# Power.net
KiCad netlist of a schematic drawn in Altium Designer
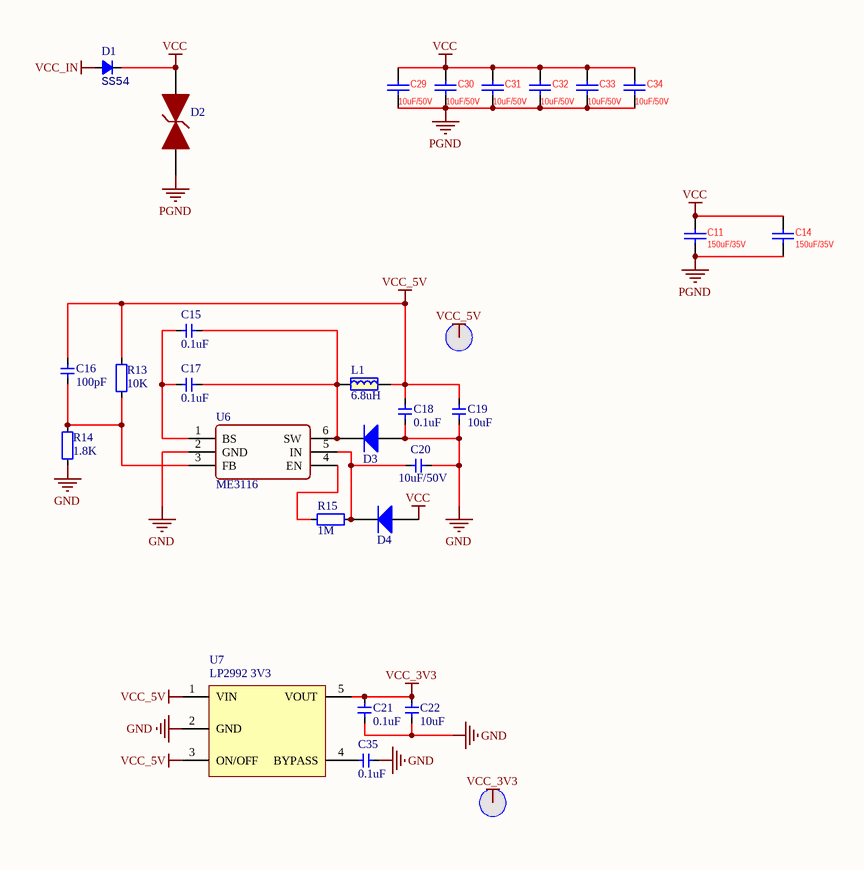
[diagram p0: Power.SchDoc]

(export (version "E")
  (design (tool "Eeschema 10.0.6"))
  (components
    (comp (ref "C11")
      (value "150uF/35V")
      (footprint "CAP-SMD_BD8.0-L8.3-W8.3-LS9.3-FD")
      (description "Capacitor, chip, ceramic")
      (fields (field (name "Comment") "220uF/25V"))
      (libsource (lib "OAKUSBFXS") (part "CAP"))
    )
    (comp (ref "C14")
      (value "150uF/35V")
      (footprint "CAP-SMD_BD8.0-L8.3-W8.3-LS9.3-FD")
      (description "Capacitor, chip, ceramic")
      (fields (field (name "Comment") "220uF/25V"))
      (libsource (lib "OAKUSBFXS") (part "CAP"))
    )
    (comp (ref "C15")
      (value "0.1uF")
      (footprint "motor42-lib:CAP_0402")
      (description "Capacitor")
      (libsource (lib "MyPcbLib") (part "电容-0402"))
    )
    (comp (ref "C16")
      (value "100pF")
      (footprint "CAP_0402")
      (description "Capacitor")
      (libsource (lib "MyPcbLib") (part "电容-0402"))
    )
    (comp (ref "C17")
      (value "0.1uF")
      (footprint "motor42-lib:CAP_0402")
      (description "Capacitor")
      (libsource (lib "MyPcbLib") (part "电容-0402"))
    )
    (comp (ref "C18")
      (value "0.1uF")
      (footprint "motor42-lib:CAP_0402")
      (description "Capacitor")
      (libsource (lib "MyPcbLib") (part "电容-0402"))
    )
    (comp (ref "C19")
      (value "10uF")
      (footprint "CAP_0402")
      (description "Capacitor")
      (libsource (lib "MyPcbLib") (part "电容-0402"))
    )
    (comp (ref "C20")
      (value "10uF/50V")
      (footprint "1206-CAP")
      (description "Capacitor")
      (libsource (lib "MyPcbLib") (part "电容-0402"))
    )
    (comp (ref "C21")
      (value "0.1uF")
      (footprint "motor42-lib:CAP_0402")
      (description "Capacitor")
      (libsource (lib "MyPcbLib") (part "电容-0402"))
    )
    (comp (ref "C22")
      (value "10uF")
      (footprint "CAP_0402")
      (description "Capacitor")
      (libsource (lib "MyPcbLib") (part "电容-0402"))
    )
    (comp (ref "C29")
      (value "10uF/50V")
      (footprint "1206-CAP")
      (description "Capacitor, chip, ceramic")
      (libsource (lib "OAKUSBFXS") (part "CAP"))
    )
    (comp (ref "C30")
      (value "10uF/50V")
      (footprint "1206-CAP")
      (description "Capacitor, chip, ceramic")
      (libsource (lib "OAKUSBFXS") (part "CAP"))
    )
    (comp (ref "C31")
      (value "10uF/50V")
      (footprint "1206-CAP")
      (description "Capacitor, chip, ceramic")
      (libsource (lib "OAKUSBFXS") (part "CAP"))
    )
    (comp (ref "C32")
      (value "10uF/50V")
      (footprint "1206-CAP")
      (description "Capacitor, chip, ceramic")
      (libsource (lib "OAKUSBFXS") (part "CAP"))
    )
    (comp (ref "C33")
      (value "10uF/50V")
      (footprint "1206-CAP")
      (description "Capacitor, chip, ceramic")
      (libsource (lib "OAKUSBFXS") (part "CAP"))
    )
    (comp (ref "C34")
      (value "10uF/50V")
      (footprint "1206-CAP")
      (description "Capacitor, chip, ceramic")
      (libsource (lib "OAKUSBFXS") (part "CAP"))
    )
    (comp (ref "C35")
      (value "0.1uF")
      (footprint "motor42-lib:CAP_0402")
      (description "Capacitor")
      (libsource (lib "MyPcbLib") (part "电容-0402"))
    )
    (comp (ref "D1")
      (value "SS54")
      (footprint "DO-214AC")
      (description "Diode")
      (libsource (lib "KitSprout") (part "Diode_SMA"))
    )
    (comp (ref "D2")
      (value "SMBJ28CA")
      (footprint "SMBJ-CA_MFG")
      (libsource (lib "MyPcbLib") (part "SMBJ28CA"))
    )
    (comp (ref "D3")
      (value "二极管-5819W")
      (footprint "SOD-323")
      (description "40V")
      (libsource (lib "MyPcbLib") (part "二极管-5819W"))
    )
    (comp (ref "D4")
      (value "二极管-5819W")
      (footprint "SOD-323")
      (description "40V")
      (libsource (lib "MyPcbLib") (part "二极管-5819W"))
    )
    (comp (ref "L1") (value "6.8uH") (footprint "IND-201612") (libsource (lib "MyPcbLib") (part "电感-201612")))
    (comp (ref "R13")
      (value "10K")
      (footprint "RES_0402")
      (description "Resistor")
      (libsource (lib "") (part "电阻-0402_1"))
    )
    (comp (ref "R14")
      (value "1.8K")
      (footprint "RES_0402")
      (description "Resistor")
      (libsource (lib "") (part "电阻-0402_1"))
    )
    (comp (ref "R15")
      (value "1M")
      (footprint "RES_0402")
      (description "Resistor")
      (libsource (lib "MyPcbLib") (part "电阻-0402"))
    )
    (comp (ref "T1") (value "测试点") (footprint "TEST_PT") (libsource (lib "MyPcbLib") (part "测试点")))
    (comp (ref "T2") (value "测试点") (footprint "TEST_PT") (libsource (lib "MyPcbLib") (part "测试点")))
    (comp (ref "U6")
      (value "ME3116")
      (footprint "SOT23-6")
      (description "DC-DC")
      (libsource (lib "MyPcbLib") (part "ME3116"))
    )
    (comp (ref "U7")
      (value "LP2992 3V3")
      (footprint "SOT23-5")
      (description "LDO")
      (libsource (lib "MyPcbLib") (part "LP2992"))
    )
  )
  (nets
    (net (code "1") (name "GND") (class "Default")
      (node (ref "C18") (pin "1") (pinfunction "1_1") (pintype "passive"))
      (node (ref "C19") (pin "1") (pinfunction "1_1") (pintype "passive"))
      (node (ref "C20") (pin "1") (pinfunction "1_1") (pintype "passive"))
      (node (ref "C21") (pin "1") (pinfunction "1_1") (pintype "passive"))
      (node (ref "C22") (pin "1") (pinfunction "1_1") (pintype "passive"))
      (node (ref "C35") (pin "1") (pinfunction "1_1") (pintype "passive"))
      (node (ref "D3") (pin "1") (pinfunction "A_1") (pintype "passive"))
      (node (ref "R14") (pin "1") (pinfunction "1_1") (pintype "passive"))
      (node (ref "U6") (pin "2") (pinfunction "GND_2") (pintype "passive"))
      (node (ref "U7") (pin "2") (pinfunction "GND_2") (pintype "passive"))
    )
    (net (code "2") (name "Net-(D3-K)") (class "Default")
      (node (ref "C15") (pin "1") (pinfunction "1_1") (pintype "passive"))
      (node (ref "C17") (pin "1") (pinfunction "1_1") (pintype "passive"))
      (node (ref "D3") (pin "2") (pinfunction "K_2") (pintype "passive"))
      (node (ref "L1") (pin "1") (pintype "passive"))
      (node (ref "U6") (pin "6") (pinfunction "SW_6") (pintype "passive"))
    )
    (net (code "3") (name "Net-(D4-K)") (class "Default")
      (node (ref "C20") (pin "2") (pinfunction "2_2") (pintype "passive"))
      (node (ref "D4") (pin "2") (pinfunction "K_2") (pintype "passive"))
      (node (ref "R15") (pin "1") (pinfunction "1_1") (pintype "passive"))
      (node (ref "U6") (pin "5") (pinfunction "IN_5") (pintype "passive"))
    )
    (net (code "4") (name "Net-(U6-BS)") (class "Default")
      (node (ref "C15") (pin "2") (pinfunction "2_2") (pintype "passive"))
      (node (ref "C17") (pin "2") (pinfunction "2_2") (pintype "passive"))
      (node (ref "U6") (pin "1") (pinfunction "BS_1") (pintype "passive"))
    )
    (net (code "5") (name "Net-(U6-EN)") (class "Default")
      (node (ref "R15") (pin "2") (pinfunction "2_2") (pintype "passive"))
      (node (ref "U6") (pin "4") (pinfunction "EN_4") (pintype "passive"))
    )
    (net (code "6") (name "Net-(U6-FB)") (class "Default")
      (node (ref "C16") (pin "2") (pinfunction "2_2") (pintype "passive"))
      (node (ref "R13") (pin "1") (pinfunction "1_1") (pintype "passive"))
      (node (ref "R14") (pin "2") (pinfunction "2_2") (pintype "passive"))
      (node (ref "U6") (pin "3") (pinfunction "FB_3") (pintype "passive"))
    )
    (net (code "7") (name "Net-(U7-BYPASS)") (class "Default")
      (node (ref "C35") (pin "2") (pinfunction "2_2") (pintype "passive"))
      (node (ref "U7") (pin "4") (pinfunction "BYPASS_4") (pintype "passive"))
    )
    (net (code "8") (name "PGND") (class "Default")
      (node (ref "C11") (pin "2") (pinfunction "2_2") (pintype "passive"))
      (node (ref "C14") (pin "2") (pinfunction "2_2") (pintype "passive"))
      (node (ref "C29") (pin "2") (pinfunction "2_2") (pintype "passive"))
      (node (ref "C30") (pin "2") (pinfunction "2_2") (pintype "passive"))
      (node (ref "C31") (pin "2") (pinfunction "2_2") (pintype "passive"))
      (node (ref "C32") (pin "2") (pinfunction "2_2") (pintype "passive"))
      (node (ref "C33") (pin "2") (pinfunction "2_2") (pintype "passive"))
      (node (ref "C34") (pin "2") (pinfunction "2_2") (pintype "passive"))
      (node (ref "D2") (pin "1") (pinfunction "1_1") (pintype "passive"))
    )
    (net (code "9") (name "VCC") (class "Default")
      (node (ref "C11") (pin "1") (pinfunction "1_1") (pintype "passive"))
      (node (ref "C14") (pin "1") (pinfunction "1_1") (pintype "passive"))
      (node (ref "C29") (pin "1") (pinfunction "1_1") (pintype "passive"))
      (node (ref "C30") (pin "1") (pinfunction "1_1") (pintype "passive"))
      (node (ref "C31") (pin "1") (pinfunction "1_1") (pintype "passive"))
      (node (ref "C32") (pin "1") (pinfunction "1_1") (pintype "passive"))
      (node (ref "C33") (pin "1") (pinfunction "1_1") (pintype "passive"))
      (node (ref "C34") (pin "1") (pinfunction "1_1") (pintype "passive"))
      (node (ref "D1") (pin "2") (pinfunction "K_2") (pintype "passive"))
      (node (ref "D2") (pin "2") (pinfunction "2_2") (pintype "passive"))
      (node (ref "D4") (pin "1") (pinfunction "A_1") (pintype "passive"))
    )
    (net (code "10") (name "VCC_3V3") (class "Default")
      (node (ref "C21") (pin "2") (pinfunction "2_2") (pintype "passive"))
      (node (ref "C22") (pin "2") (pinfunction "2_2") (pintype "passive"))
      (node (ref "T2") (pin "0") (pinfunction "0_0") (pintype "passive"))
      (node (ref "U7") (pin "5") (pinfunction "VOUT_5") (pintype "passive"))
    )
    (net (code "11") (name "VCC_5V") (class "Default")
      (node (ref "C16") (pin "1") (pinfunction "1_1") (pintype "passive"))
      (node (ref "C18") (pin "2") (pinfunction "2_2") (pintype "passive"))
      (node (ref "C19") (pin "2") (pinfunction "2_2") (pintype "passive"))
      (node (ref "L1") (pin "2") (pinfunction "2_2") (pintype "passive"))
      (node (ref "R13") (pin "2") (pinfunction "2_2") (pintype "passive"))
      (node (ref "T1") (pin "0") (pinfunction "0_0") (pintype "passive"))
      (node (ref "U7") (pin "1") (pinfunction "VIN_1") (pintype "passive"))
      (node (ref "U7") (pin "3") (pinfunction "ON/OFF_3") (pintype "passive"))
    )
    (net (code "12") (name "VCC_IN") (class "Default")
      (node (ref "D1") (pin "1") (pinfunction "A_1") (pintype "passive"))
    )
  )
)
